# CONNECTOR.net
KiCad netlist of a schematic drawn in Altium Designer
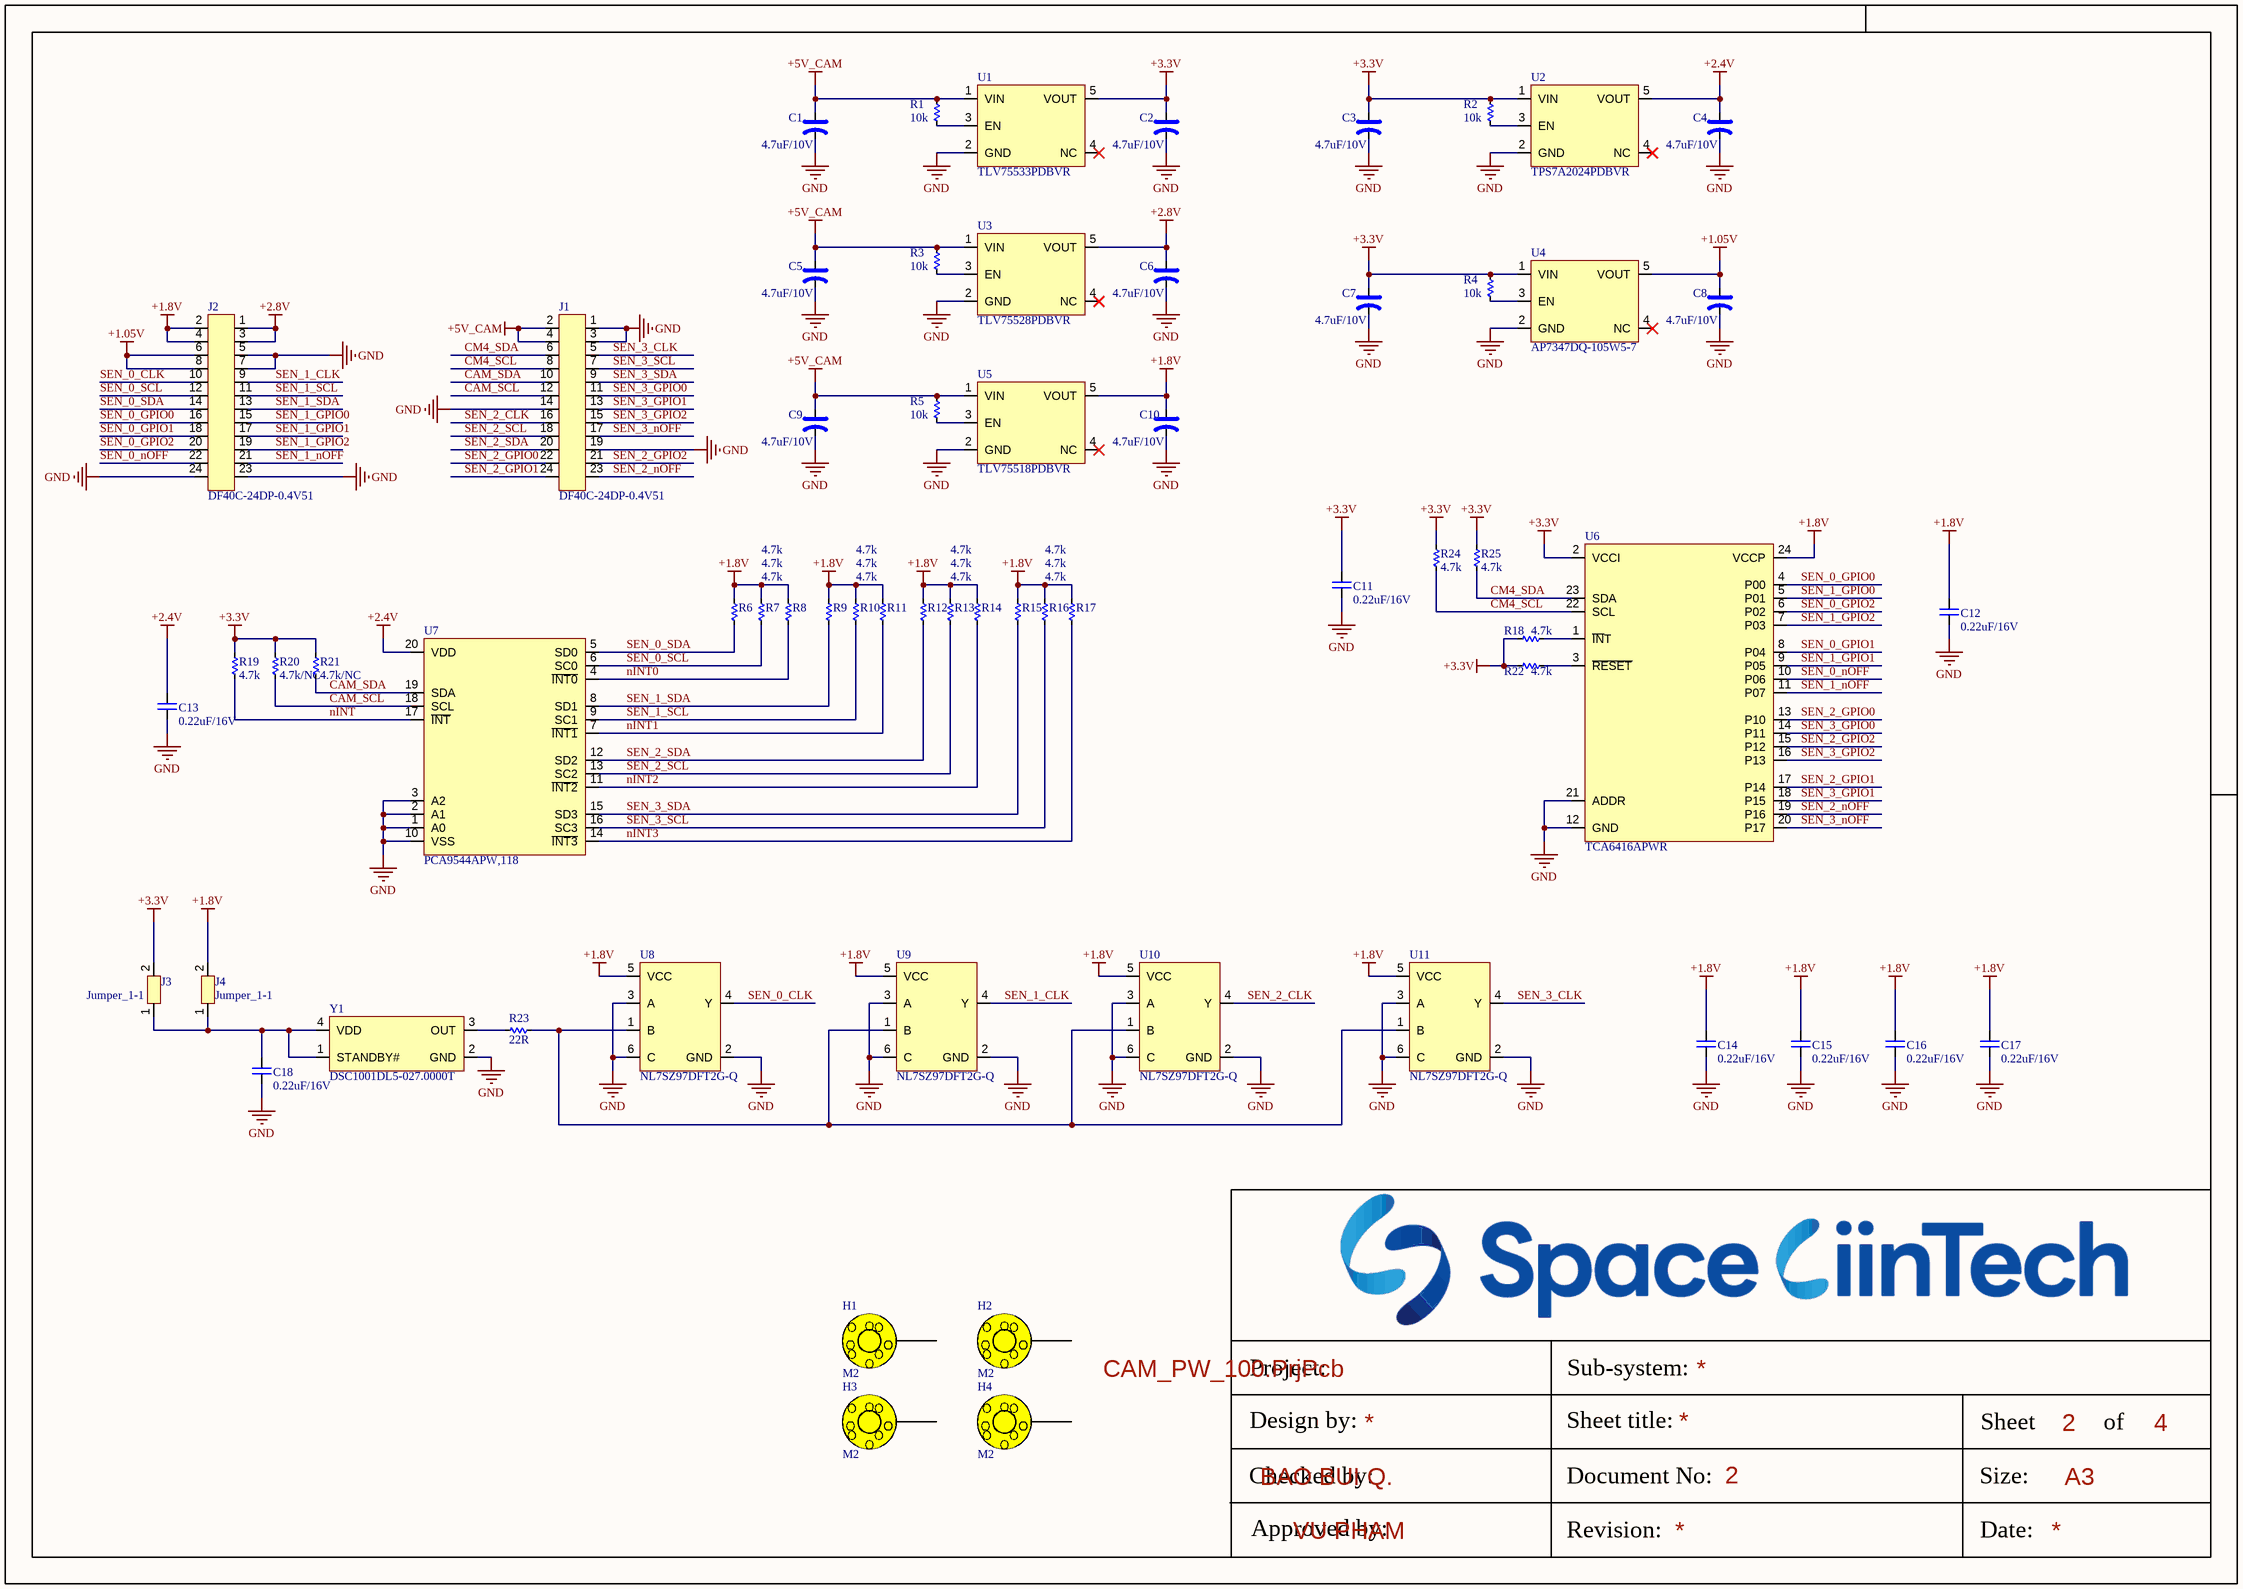
[diagram p0: CONNECTOR.SchDoc]

(export (version "E")
  (design (tool "Eeschema 10.0.6"))
  (components
    (comp (ref "C1")
      (value "4.7uF/10V")
      (footprint "CAP_MP_1608X90")
      (description "CAP_Polarization")
      (fields (field (name "PUBLISHER") "Altium Limited"))
      (libsource (lib "LABLIB") (part "CAP_TH"))
    )
    (comp (ref "C2")
      (value "4.7uF/10V")
      (footprint "CAP_MP_1608X90")
      (description "CAP_Polarization")
      (fields (field (name "PUBLISHER") "Altium Limited"))
      (libsource (lib "LABLIB") (part "CAP_TH"))
    )
    (comp (ref "C3")
      (value "4.7uF/10V")
      (footprint "CAP_MP_1608X90")
      (description "CAP_Polarization")
      (fields (field (name "PUBLISHER") "Altium Limited"))
      (libsource (lib "LABLIB") (part "CAP_TH"))
    )
    (comp (ref "C4")
      (value "4.7uF/10V")
      (footprint "CAP_MP_1608X90")
      (description "CAP_Polarization")
      (fields (field (name "PUBLISHER") "Altium Limited"))
      (libsource (lib "LABLIB") (part "CAP_TH"))
    )
    (comp (ref "C5")
      (value "4.7uF/10V")
      (footprint "CAP_MP_1608X90")
      (description "CAP_Polarization")
      (fields (field (name "PUBLISHER") "Altium Limited"))
      (libsource (lib "LABLIB") (part "CAP_TH"))
    )
    (comp (ref "C6")
      (value "4.7uF/10V")
      (footprint "CAP_MP_1608X90")
      (description "CAP_Polarization")
      (fields (field (name "PUBLISHER") "Altium Limited"))
      (libsource (lib "LABLIB") (part "CAP_TH"))
    )
    (comp (ref "C7")
      (value "4.7uF/10V")
      (footprint "CAP_MP_1608X90")
      (description "CAP_Polarization")
      (fields (field (name "PUBLISHER") "Altium Limited"))
      (libsource (lib "LABLIB") (part "CAP_TH"))
    )
    (comp (ref "C8")
      (value "4.7uF/10V")
      (footprint "CAP_MP_1608X90")
      (description "CAP_Polarization")
      (fields (field (name "PUBLISHER") "Altium Limited"))
      (libsource (lib "LABLIB") (part "CAP_TH"))
    )
    (comp (ref "C9")
      (value "4.7uF/10V")
      (footprint "CAP_MP_1608X90")
      (description "CAP_Polarization")
      (fields (field (name "PUBLISHER") "Altium Limited"))
      (libsource (lib "LABLIB") (part "CAP_TH"))
    )
    (comp (ref "C10")
      (value "4.7uF/10V")
      (footprint "CAP_MP_1608X90")
      (description "CAP_Polarization")
      (fields (field (name "PUBLISHER") "Altium Limited"))
      (libsource (lib "LABLIB") (part "CAP_TH"))
    )
    (comp (ref "C11")
      (value "0.22uF/16V")
      (footprint "CAP_C_1005X60")
      (description "CAP_Chip")
      (libsource (lib "LABLIB") (part "CAP_SMD"))
    )
    (comp (ref "C12")
      (value "0.22uF/16V")
      (footprint "CAP_C_1005X60")
      (description "CAP_Chip")
      (libsource (lib "LABLIB") (part "CAP_SMD"))
    )
    (comp (ref "C13")
      (value "0.22uF/16V")
      (footprint "CAP_C_1005X60")
      (description "CAP_Chip")
      (libsource (lib "LABLIB") (part "CAP_SMD"))
    )
    (comp (ref "C14")
      (value "0.22uF/16V")
      (footprint "CAP_C_1005X60")
      (description "CAP_Chip")
      (libsource (lib "LABLIB") (part "CAP_SMD"))
    )
    (comp (ref "C15")
      (value "0.22uF/16V")
      (footprint "CAP_C_1005X60")
      (description "CAP_Chip")
      (libsource (lib "LABLIB") (part "CAP_SMD"))
    )
    (comp (ref "C16")
      (value "0.22uF/16V")
      (footprint "CAP_C_1005X60")
      (description "CAP_Chip")
      (libsource (lib "LABLIB") (part "CAP_SMD"))
    )
    (comp (ref "C17")
      (value "0.22uF/16V")
      (footprint "CAP_C_1005X60")
      (description "CAP_Chip")
      (libsource (lib "LABLIB") (part "CAP_SMD"))
    )
    (comp (ref "C18")
      (value "0.22uF/16V")
      (footprint "CAP_C_1005X60")
      (description "CAP_Chip")
      (libsource (lib "LABLIB") (part "CAP_SMD"))
    )
    (comp (ref "H1") (value "M2") (footprint "HEX-2.2mm") (libsource (lib "hex_M3") (part "HEX-M3")))
    (comp (ref "H2") (value "M2") (footprint "HEX-2.2mm") (libsource (lib "hex_M3") (part "HEX-M3")))
    (comp (ref "H3") (value "M2") (footprint "HEX-2.2mm") (libsource (lib "hex_M3") (part "HEX-M3")))
    (comp (ref "H4") (value "M2") (footprint "HEX-2.2mm") (libsource (lib "hex_M3") (part "HEX-M3")))
    (comp (ref "J1")
      (value "DF40C-24DP-0.4V51")
      (footprint "CONN24_6p32X1p85_hdr_HIR")
      (description "No Description Available")
      (libsource (lib "CAMERA_SchLib") (part "DF40C-24DP-0.4V51"))
    )
    (comp (ref "J2")
      (value "DF40C-24DP-0.4V51")
      (footprint "CONN24_6p32X1p85_hdr_HIR")
      (description "No Description Available")
      (libsource (lib "CAMERA_SchLib") (part "DF40C-24DP-0.4V51"))
    )
    (comp (ref "J3")
      (value "Jumper_1-1")
      (footprint "Jumper_1-1")
      (libsource (lib "CAMERA_SchLib") (part "Jumper_1_1"))
    )
    (comp (ref "J4")
      (value "Jumper_1-1")
      (footprint "Jumper_1-1")
      (libsource (lib "CAMERA_SchLib") (part "Jumper_1_1"))
    )
    (comp (ref "R1")
      (value "10k")
      (footprint "RES_C_1005X40")
      (description "RES-Chip")
      (fields
        (field (name "MANUFACTURER") "Generic Components")
        (field (name "PUBLISHER") "Altium Hobart Technology Centre")
      )
      (libsource (lib "LABLIB") (part "RES-SMD"))
    )
    (comp (ref "R2")
      (value "10k")
      (footprint "RES_C_1005X40")
      (description "RES-Chip")
      (fields
        (field (name "MANUFACTURER") "Generic Components")
        (field (name "PUBLISHER") "Altium Hobart Technology Centre")
      )
      (libsource (lib "LABLIB") (part "RES-SMD"))
    )
    (comp (ref "R3")
      (value "10k")
      (footprint "RES_C_1005X40")
      (description "RES-Chip")
      (fields
        (field (name "MANUFACTURER") "Generic Components")
        (field (name "PUBLISHER") "Altium Hobart Technology Centre")
      )
      (libsource (lib "LABLIB") (part "RES-SMD"))
    )
    (comp (ref "R4")
      (value "10k")
      (footprint "RES_C_1005X40")
      (description "RES-Chip")
      (fields
        (field (name "MANUFACTURER") "Generic Components")
        (field (name "PUBLISHER") "Altium Hobart Technology Centre")
      )
      (libsource (lib "LABLIB") (part "RES-SMD"))
    )
    (comp (ref "R5")
      (value "10k")
      (footprint "RES_C_1005X40")
      (description "RES-Chip")
      (fields
        (field (name "MANUFACTURER") "Generic Components")
        (field (name "PUBLISHER") "Altium Hobart Technology Centre")
      )
      (libsource (lib "LABLIB") (part "RES-SMD"))
    )
    (comp (ref "R6")
      (value "4.7k")
      (footprint "RES_C_1005X40")
      (description "RES-Chip")
      (fields
        (field (name "MANUFACTURER") "Generic Components")
        (field (name "PUBLISHER") "Altium Hobart Technology Centre")
      )
      (libsource (lib "LABLIB") (part "RES-SMD"))
    )
    (comp (ref "R7")
      (value "4.7k")
      (footprint "RES_C_1005X40")
      (description "RES-Chip")
      (fields
        (field (name "MANUFACTURER") "Generic Components")
        (field (name "PUBLISHER") "Altium Hobart Technology Centre")
      )
      (libsource (lib "LABLIB") (part "RES-SMD"))
    )
    (comp (ref "R8")
      (value "4.7k")
      (footprint "RES_C_1005X40")
      (description "RES-Chip")
      (fields
        (field (name "MANUFACTURER") "Generic Components")
        (field (name "PUBLISHER") "Altium Hobart Technology Centre")
      )
      (libsource (lib "LABLIB") (part "RES-SMD"))
    )
    (comp (ref "R9")
      (value "4.7k")
      (footprint "RES_C_1005X40")
      (description "RES-Chip")
      (fields
        (field (name "MANUFACTURER") "Generic Components")
        (field (name "PUBLISHER") "Altium Hobart Technology Centre")
      )
      (libsource (lib "LABLIB") (part "RES-SMD"))
    )
    (comp (ref "R10")
      (value "4.7k")
      (footprint "RES_C_1005X40")
      (description "RES-Chip")
      (fields
        (field (name "MANUFACTURER") "Generic Components")
        (field (name "PUBLISHER") "Altium Hobart Technology Centre")
      )
      (libsource (lib "LABLIB") (part "RES-SMD"))
    )
    (comp (ref "R11")
      (value "4.7k")
      (footprint "RES_C_1005X40")
      (description "RES-Chip")
      (fields
        (field (name "MANUFACTURER") "Generic Components")
        (field (name "PUBLISHER") "Altium Hobart Technology Centre")
      )
      (libsource (lib "LABLIB") (part "RES-SMD"))
    )
    (comp (ref "R12")
      (value "4.7k")
      (footprint "RES_C_1005X40")
      (description "RES-Chip")
      (fields
        (field (name "MANUFACTURER") "Generic Components")
        (field (name "PUBLISHER") "Altium Hobart Technology Centre")
      )
      (libsource (lib "LABLIB") (part "RES-SMD"))
    )
    (comp (ref "R13")
      (value "4.7k")
      (footprint "RES_C_1005X40")
      (description "RES-Chip")
      (fields
        (field (name "MANUFACTURER") "Generic Components")
        (field (name "PUBLISHER") "Altium Hobart Technology Centre")
      )
      (libsource (lib "LABLIB") (part "RES-SMD"))
    )
    (comp (ref "R14")
      (value "4.7k")
      (footprint "RES_C_1005X40")
      (description "RES-Chip")
      (fields
        (field (name "MANUFACTURER") "Generic Components")
        (field (name "PUBLISHER") "Altium Hobart Technology Centre")
      )
      (libsource (lib "LABLIB") (part "RES-SMD"))
    )
    (comp (ref "R15")
      (value "4.7k")
      (footprint "RES_C_1005X40")
      (description "RES-Chip")
      (fields
        (field (name "MANUFACTURER") "Generic Components")
        (field (name "PUBLISHER") "Altium Hobart Technology Centre")
      )
      (libsource (lib "LABLIB") (part "RES-SMD"))
    )
    (comp (ref "R16")
      (value "4.7k")
      (footprint "RES_C_1005X40")
      (description "RES-Chip")
      (fields
        (field (name "MANUFACTURER") "Generic Components")
        (field (name "PUBLISHER") "Altium Hobart Technology Centre")
      )
      (libsource (lib "LABLIB") (part "RES-SMD"))
    )
    (comp (ref "R17")
      (value "4.7k")
      (footprint "RES_C_1005X40")
      (description "RES-Chip")
      (fields
        (field (name "MANUFACTURER") "Generic Components")
        (field (name "PUBLISHER") "Altium Hobart Technology Centre")
      )
      (libsource (lib "LABLIB") (part "RES-SMD"))
    )
    (comp (ref "R18")
      (value "4.7k")
      (footprint "RES_C_1005X40")
      (description "RES-Chip")
      (fields
        (field (name "MANUFACTURER") "Generic Components")
        (field (name "PUBLISHER") "Altium Hobart Technology Centre")
      )
      (libsource (lib "LABLIB") (part "RES-SMD"))
    )
    (comp (ref "R19")
      (value "4.7k")
      (footprint "RES_C_1005X40")
      (description "RES-Chip")
      (fields
        (field (name "MANUFACTURER") "Generic Components")
        (field (name "PUBLISHER") "Altium Hobart Technology Centre")
      )
      (libsource (lib "LABLIB") (part "RES-SMD"))
    )
    (comp (ref "R20")
      (value "4.7k/NC")
      (footprint "RES_C_1005X40")
      (description "RES-Chip")
      (fields
        (field (name "MANUFACTURER") "Generic Components")
        (field (name "PUBLISHER") "Altium Hobart Technology Centre")
      )
      (libsource (lib "LABLIB") (part "RES-SMD"))
    )
    (comp (ref "R21")
      (value "4.7k/NC")
      (footprint "RES_C_1005X40")
      (description "RES-Chip")
      (fields
        (field (name "MANUFACTURER") "Generic Components")
        (field (name "PUBLISHER") "Altium Hobart Technology Centre")
      )
      (libsource (lib "LABLIB") (part "RES-SMD"))
    )
    (comp (ref "R22")
      (value "4.7k")
      (footprint "RES_C_1005X40")
      (description "RES-Chip")
      (fields
        (field (name "MANUFACTURER") "Generic Components")
        (field (name "PUBLISHER") "Altium Hobart Technology Centre")
      )
      (libsource (lib "LABLIB") (part "RES-SMD"))
    )
    (comp (ref "R23")
      (value "22R")
      (footprint "RES_C_1005X40")
      (description "RES-Chip")
      (fields
        (field (name "MANUFACTURER") "Generic Components")
        (field (name "PUBLISHER") "Altium Hobart Technology Centre")
      )
      (libsource (lib "LABLIB") (part "RES-SMD"))
    )
    (comp (ref "R24")
      (value "4.7k")
      (footprint "RES_C_1005X40")
      (description "RES-Chip")
      (fields
        (field (name "MANUFACTURER") "Generic Components")
        (field (name "PUBLISHER") "Altium Hobart Technology Centre")
      )
      (libsource (lib "LABLIB") (part "RES-SMD"))
    )
    (comp (ref "R25")
      (value "4.7k")
      (footprint "RES_C_1005X40")
      (description "RES-Chip")
      (fields
        (field (name "MANUFACTURER") "Generic Components")
        (field (name "PUBLISHER") "Altium Hobart Technology Centre")
      )
      (libsource (lib "LABLIB") (part "RES-SMD"))
    )
    (comp (ref "U1")
      (value "TLV75533PDBVR")
      (footprint "SOT25")
      (libsource (lib "CAMERA_SchLib") (part "IC_POWER_AP7347DQ"))
    )
    (comp (ref "U2")
      (value "TPS7A2024PDBVR")
      (footprint "SOT25")
      (libsource (lib "CAMERA_SchLib") (part "IC_POWER_AP7347DQ"))
    )
    (comp (ref "U3")
      (value "TLV75528PDBVR")
      (footprint "SOT25")
      (libsource (lib "CAMERA_SchLib") (part "IC_POWER_AP7347DQ"))
    )
    (comp (ref "U4")
      (value "AP7347DQ-105W5-7")
      (footprint "SOT25")
      (libsource (lib "CAMERA_SchLib") (part "IC_POWER_AP7347DQ"))
    )
    (comp (ref "U5")
      (value "TLV75518PDBVR")
      (footprint "SOT25")
      (libsource (lib "CAMERA_SchLib") (part "IC_POWER_AP7347DQ"))
    )
    (comp (ref "U6")
      (value "TCA6416APWR")
      (footprint "SOP65P440W-24N")
      (libsource (lib "CAMERA_SchLib") (part "IC_I2Cto16IO_TCA6416APWR"))
    )
    (comp (ref "U7")
      (value "PCA9544APW,118")
      (footprint "SOP65P440W_20")
      (libsource (lib "CAMERA_SchLib") (part "IC_I2CSW1to4_PCA9544APW,118"))
    )
    (comp (ref "U8")
      (value "NL7SZ97DFT2G-Q")
      (footprint "SC-88")
      (libsource (lib "CAMERA_SchLib") (part "IC_FLEXLOGIC_NL7SZ97DFT2G-Q"))
    )
    (comp (ref "U9")
      (value "NL7SZ97DFT2G-Q")
      (footprint "SC-88")
      (libsource (lib "CAMERA_SchLib") (part "IC_FLEXLOGIC_NL7SZ97DFT2G-Q"))
    )
    (comp (ref "U10")
      (value "NL7SZ97DFT2G-Q")
      (footprint "SC-88")
      (libsource (lib "CAMERA_SchLib") (part "IC_FLEXLOGIC_NL7SZ97DFT2G-Q"))
    )
    (comp (ref "U11")
      (value "NL7SZ97DFT2G-Q")
      (footprint "SC-88")
      (libsource (lib "CAMERA_SchLib") (part "IC_FLEXLOGIC_NL7SZ97DFT2G-Q"))
    )
    (comp (ref "Y1")
      (value "DSC1001DL5-027.0000T")
      (footprint "OSCDFN250X200X89-4N")
      (libsource (lib "CAMERA_SchLib") (part "Y_OSC27MHz_DSC1001DL5-027.0000T"))
    )
  )
  (nets
    (net (code "1") (name "+1.05V") (class "Default")
      (node (ref "C8") (pin "1") (pinfunction "1_1") (pintype "passive"))
      (node (ref "J2") (pin "6") (pintype "passive"))
      (node (ref "J2") (pin "8") (pintype "passive"))
      (node (ref "U4") (pin "5") (pinfunction "VOUT_5") (pintype "passive"))
    )
    (net (code "2") (name "+1.8V") (class "Default")
      (node (ref "C10") (pin "1") (pinfunction "1_1") (pintype "passive"))
      (node (ref "C12") (pin "2") (pinfunction "2_2") (pintype "passive"))
      (node (ref "C14") (pin "2") (pinfunction "2_2") (pintype "passive"))
      (node (ref "C15") (pin "2") (pinfunction "2_2") (pintype "passive"))
      (node (ref "C16") (pin "2") (pinfunction "2_2") (pintype "passive"))
      (node (ref "C17") (pin "2") (pinfunction "2_2") (pintype "passive"))
      (node (ref "J2") (pin "2") (pintype "passive"))
      (node (ref "J2") (pin "4") (pintype "passive"))
      (node (ref "J4") (pin "2") (pintype "passive"))
      (node (ref "R10") (pin "1") (pinfunction "1_1") (pintype "passive"))
      (node (ref "R11") (pin "1") (pinfunction "1_1") (pintype "passive"))
      (node (ref "R12") (pin "1") (pinfunction "1_1") (pintype "passive"))
      (node (ref "R13") (pin "1") (pinfunction "1_1") (pintype "passive"))
      (node (ref "R14") (pin "1") (pinfunction "1_1") (pintype "passive"))
      (node (ref "R15") (pin "1") (pinfunction "1_1") (pintype "passive"))
      (node (ref "R16") (pin "1") (pinfunction "1_1") (pintype "passive"))
      (node (ref "R17") (pin "1") (pinfunction "1_1") (pintype "passive"))
      (node (ref "R6") (pin "1") (pinfunction "1_1") (pintype "passive"))
      (node (ref "R7") (pin "1") (pinfunction "1_1") (pintype "passive"))
      (node (ref "R8") (pin "1") (pinfunction "1_1") (pintype "passive"))
      (node (ref "R9") (pin "1") (pinfunction "1_1") (pintype "passive"))
      (node (ref "U10") (pin "5") (pinfunction "VCC_5") (pintype "passive"))
      (node (ref "U11") (pin "5") (pinfunction "VCC_5") (pintype "passive"))
      (node (ref "U5") (pin "5") (pinfunction "VOUT_5") (pintype "passive"))
      (node (ref "U6") (pin "24") (pinfunction "VCCP_24") (pintype "passive"))
      (node (ref "U8") (pin "5") (pinfunction "VCC_5") (pintype "passive"))
      (node (ref "U9") (pin "5") (pinfunction "VCC_5") (pintype "passive"))
    )
    (net (code "3") (name "+2.4V") (class "Default")
      (node (ref "C13") (pin "2") (pinfunction "2_2") (pintype "passive"))
      (node (ref "C4") (pin "1") (pinfunction "1_1") (pintype "passive"))
      (node (ref "U2") (pin "5") (pinfunction "VOUT_5") (pintype "passive"))
      (node (ref "U7") (pin "20") (pinfunction "VDD_20") (pintype "passive"))
    )
    (net (code "4") (name "+2.8V") (class "Default")
      (node (ref "C6") (pin "1") (pinfunction "1_1") (pintype "passive"))
      (node (ref "J2") (pin "1") (pintype "passive"))
      (node (ref "J2") (pin "3") (pintype "passive"))
      (node (ref "U3") (pin "5") (pinfunction "VOUT_5") (pintype "passive"))
    )
    (net (code "5") (name "+3.3V") (class "Default")
      (node (ref "C11") (pin "2") (pinfunction "2_2") (pintype "passive"))
      (node (ref "C2") (pin "1") (pinfunction "1_1") (pintype "passive"))
      (node (ref "C3") (pin "1") (pinfunction "1_1") (pintype "passive"))
      (node (ref "C7") (pin "1") (pinfunction "1_1") (pintype "passive"))
      (node (ref "J3") (pin "2") (pintype "passive"))
      (node (ref "R18") (pin "1") (pinfunction "1_1") (pintype "passive"))
      (node (ref "R19") (pin "1") (pinfunction "1_1") (pintype "passive"))
      (node (ref "R2") (pin "2") (pinfunction "2_2") (pintype "passive"))
      (node (ref "R20") (pin "1") (pinfunction "1_1") (pintype "passive"))
      (node (ref "R21") (pin "1") (pinfunction "1_1") (pintype "passive"))
      (node (ref "R22") (pin "1") (pinfunction "1_1") (pintype "passive"))
      (node (ref "R24") (pin "1") (pinfunction "1_1") (pintype "passive"))
      (node (ref "R25") (pin "1") (pinfunction "1_1") (pintype "passive"))
      (node (ref "R4") (pin "2") (pinfunction "2_2") (pintype "passive"))
      (node (ref "U1") (pin "5") (pinfunction "VOUT_5") (pintype "passive"))
      (node (ref "U2") (pin "1") (pinfunction "VIN_1") (pintype "passive"))
      (node (ref "U4") (pin "1") (pinfunction "VIN_1") (pintype "passive"))
      (node (ref "U6") (pin "2") (pinfunction "VCCI_2") (pintype "passive"))
    )
    (net (code "6") (name "+5V_CAM") (class "Default")
      (node (ref "C1") (pin "1") (pinfunction "1_1") (pintype "passive"))
      (node (ref "C5") (pin "1") (pinfunction "1_1") (pintype "passive"))
      (node (ref "C9") (pin "1") (pinfunction "1_1") (pintype "passive"))
      (node (ref "J1") (pin "2") (pintype "passive"))
      (node (ref "J1") (pin "4") (pintype "passive"))
      (node (ref "R1") (pin "2") (pinfunction "2_2") (pintype "passive"))
      (node (ref "R3") (pin "2") (pinfunction "2_2") (pintype "passive"))
      (node (ref "R5") (pin "2") (pinfunction "2_2") (pintype "passive"))
      (node (ref "U1") (pin "1") (pinfunction "VIN_1") (pintype "passive"))
      (node (ref "U3") (pin "1") (pinfunction "VIN_1") (pintype "passive"))
      (node (ref "U5") (pin "1") (pinfunction "VIN_1") (pintype "passive"))
    )
    (net (code "7") (name "/CAM_SCL") (class "Default")
      (node (ref "J1") (pin "12") (pintype "passive"))
      (node (ref "R20") (pin "2") (pinfunction "2_2") (pintype "passive"))
      (node (ref "U7") (pin "18") (pinfunction "SCL_18") (pintype "passive"))
    )
    (net (code "8") (name "/CAM_SDA") (class "Default")
      (node (ref "J1") (pin "10") (pintype "passive"))
      (node (ref "R21") (pin "2") (pinfunction "2_2") (pintype "passive"))
      (node (ref "U7") (pin "19") (pinfunction "SDA_19") (pintype "passive"))
    )
    (net (code "9") (name "/CM4_SCL") (class "Default")
      (node (ref "J1") (pin "8") (pintype "passive"))
      (node (ref "R24") (pin "2") (pinfunction "2_2") (pintype "passive"))
      (node (ref "U6") (pin "22") (pinfunction "SCL_22") (pintype "passive"))
    )
    (net (code "10") (name "/CM4_SDA") (class "Default")
      (node (ref "J1") (pin "6") (pintype "passive"))
      (node (ref "R25") (pin "2") (pinfunction "2_2") (pintype "passive"))
      (node (ref "U6") (pin "23") (pinfunction "SDA_23") (pintype "passive"))
    )
    (net (code "11") (name "/SEN_0_CLK") (class "Default")
      (node (ref "J2") (pin "10") (pintype "passive"))
      (node (ref "U8") (pin "4") (pinfunction "Y_4") (pintype "passive"))
    )
    (net (code "12") (name "/SEN_0_GPIO0") (class "Default")
      (node (ref "J2") (pin "16") (pintype "passive"))
      (node (ref "U6") (pin "4") (pinfunction "P00_4") (pintype "passive"))
    )
    (net (code "13") (name "/SEN_0_GPIO1") (class "Default")
      (node (ref "J2") (pin "18") (pintype "passive"))
      (node (ref "U6") (pin "8") (pinfunction "P04_8") (pintype "passive"))
    )
    (net (code "14") (name "/SEN_0_GPIO2") (class "Default")
      (node (ref "J2") (pin "20") (pintype "passive"))
      (node (ref "U6") (pin "6") (pinfunction "P02_6") (pintype "passive"))
    )
    (net (code "15") (name "/SEN_0_SCL") (class "Default")
      (node (ref "J2") (pin "12") (pintype "passive"))
      (node (ref "R7") (pin "2") (pinfunction "2_2") (pintype "passive"))
      (node (ref "U7") (pin "6") (pinfunction "SC0_6") (pintype "passive"))
    )
    (net (code "16") (name "/SEN_0_SDA") (class "Default")
      (node (ref "J2") (pin "14") (pintype "passive"))
      (node (ref "R6") (pin "2") (pinfunction "2_2") (pintype "passive"))
      (node (ref "U7") (pin "5") (pinfunction "SD0_5") (pintype "passive"))
    )
    (net (code "17") (name "/SEN_0_nOFF") (class "Default")
      (node (ref "J2") (pin "22") (pintype "passive"))
      (node (ref "U6") (pin "10") (pinfunction "P06_10") (pintype "passive"))
    )
    (net (code "18") (name "/SEN_1_CLK") (class "Default")
      (node (ref "J2") (pin "9") (pintype "passive"))
      (node (ref "U9") (pin "4") (pinfunction "Y_4") (pintype "passive"))
    )
    (net (code "19") (name "/SEN_1_GPIO0") (class "Default")
      (node (ref "J2") (pin "15") (pintype "passive"))
      (node (ref "U6") (pin "5") (pinfunction "P01_5") (pintype "passive"))
    )
    (net (code "20") (name "/SEN_1_GPIO1") (class "Default")
      (node (ref "J2") (pin "17") (pintype "passive"))
      (node (ref "U6") (pin "9") (pinfunction "P05_9") (pintype "passive"))
    )
    (net (code "21") (name "/SEN_1_GPIO2") (class "Default")
      (node (ref "J2") (pin "19") (pintype "passive"))
      (node (ref "U6") (pin "7") (pinfunction "P03_7") (pintype "passive"))
    )
    (net (code "22") (name "/SEN_1_SCL") (class "Default")
      (node (ref "J2") (pin "11") (pintype "passive"))
      (node (ref "R10") (pin "2") (pinfunction "2_2") (pintype "passive"))
      (node (ref "U7") (pin "9") (pinfunction "SC1_9") (pintype "passive"))
    )
    (net (code "23") (name "/SEN_1_SDA") (class "Default")
      (node (ref "J2") (pin "13") (pintype "passive"))
      (node (ref "R9") (pin "2") (pinfunction "2_2") (pintype "passive"))
      (node (ref "U7") (pin "8") (pinfunction "SD1_8") (pintype "passive"))
    )
    (net (code "24") (name "/SEN_1_nOFF") (class "Default")
      (node (ref "J2") (pin "21") (pintype "passive"))
      (node (ref "U6") (pin "11") (pinfunction "P07_11") (pintype "passive"))
    )
    (net (code "25") (name "/SEN_2_CLK") (class "Default")
      (node (ref "J1") (pin "16") (pintype "passive"))
      (node (ref "U10") (pin "4") (pinfunction "Y_4") (pintype "passive"))
    )
    (net (code "26") (name "/SEN_2_GPIO0") (class "Default")
      (node (ref "J1") (pin "22") (pintype "passive"))
      (node (ref "U6") (pin "13") (pinfunction "P10_13") (pintype "passive"))
    )
    (net (code "27") (name "/SEN_2_GPIO1") (class "Default")
      (node (ref "J1") (pin "24") (pintype "passive"))
      (node (ref "U6") (pin "17") (pinfunction "P14_17") (pintype "passive"))
    )
    (net (code "28") (name "/SEN_2_GPIO2") (class "Default")
      (node (ref "J1") (pin "21") (pintype "passive"))
      (node (ref "U6") (pin "15") (pinfunction "P12_15") (pintype "passive"))
    )
    (net (code "29") (name "/SEN_2_SCL") (class "Default")
      (node (ref "J1") (pin "18") (pintype "passive"))
      (node (ref "R13") (pin "2") (pinfunction "2_2") (pintype "passive"))
      (node (ref "U7") (pin "13") (pinfunction "SC2_13") (pintype "passive"))
    )
    (net (code "30") (name "/SEN_2_SDA") (class "Default")
      (node (ref "J1") (pin "20") (pintype "passive"))
      (node (ref "R12") (pin "2") (pinfunction "2_2") (pintype "passive"))
      (node (ref "U7") (pin "12") (pinfunction "SD2_12") (pintype "passive"))
    )
    (net (code "31") (name "/SEN_2_nOFF") (class "Default")
      (node (ref "J1") (pin "23") (pintype "passive"))
      (node (ref "U6") (pin "19") (pinfunction "P16_19") (pintype "passive"))
    )
    (net (code "32") (name "/SEN_3_CLK") (class "Default")
      (node (ref "J1") (pin "5") (pintype "passive"))
      (node (ref "U11") (pin "4") (pinfunction "Y_4") (pintype "passive"))
    )
    (net (code "33") (name "/SEN_3_GPIO0") (class "Default")
      (node (ref "J1") (pin "11") (pintype "passive"))
      (node (ref "U6") (pin "14") (pinfunction "P11_14") (pintype "passive"))
    )
    (net (code "34") (name "/SEN_3_GPIO1") (class "Default")
      (node (ref "J1") (pin "13") (pintype "passive"))
      (node (ref "U6") (pin "18") (pinfunction "P15_18") (pintype "passive"))
    )
    (net (code "35") (name "/SEN_3_GPIO2") (class "Default")
      (node (ref "J1") (pin "15") (pintype "passive"))
      (node (ref "U6") (pin "16") (pinfunction "P13_16") (pintype "passive"))
    )
    (net (code "36") (name "/SEN_3_SCL") (class "Default")
      (node (ref "J1") (pin "7") (pintype "passive"))
      (node (ref "R16") (pin "2") (pinfunction "2_2") (pintype "passive"))
      (node (ref "U7") (pin "16") (pinfunction "SC3_16") (pintype "passive"))
    )
    (net (code "37") (name "/SEN_3_SDA") (class "Default")
      (node (ref "J1") (pin "9") (pintype "passive"))
      (node (ref "R15") (pin "2") (pinfunction "2_2") (pintype "passive"))
      (node (ref "U7") (pin "15") (pinfunction "SD3_15") (pintype "passive"))
    )
    (net (code "38") (name "/SEN_3_nOFF") (class "Default")
      (node (ref "J1") (pin "17") (pintype "passive"))
      (node (ref "U6") (pin "20") (pinfunction "P17_20") (pintype "passive"))
    )
    (net (code "39") (name "/nINT") (class "Default")
      (node (ref "R19") (pin "2") (pinfunction "2_2") (pintype "passive"))
      (node (ref "U7") (pin "17") (pinfunction "~{INT}_17") (pintype "passive"))
    )
    (net (code "40") (name "/nINT0") (class "Default")
      (node (ref "R8") (pin "2") (pinfunction "2_2") (pintype "passive"))
      (node (ref "U7") (pin "4") (pinfunction "~{INT0}_4") (pintype "passive"))
    )
    (net (code "41") (name "/nINT1") (class "Default")
      (node (ref "R11") (pin "2") (pinfunction "2_2") (pintype "passive"))
      (node (ref "U7") (pin "7") (pinfunction "~{INT1}_7") (pintype "passive"))
    )
    (net (code "42") (name "/nINT2") (class "Default")
      (node (ref "R14") (pin "2") (pinfunction "2_2") (pintype "passive"))
      (node (ref "U7") (pin "11") (pinfunction "~{INT2}_11") (pintype "passive"))
    )
    (net (code "43") (name "/nINT3") (class "Default")
      (node (ref "R17") (pin "2") (pinfunction "2_2") (pintype "passive"))
      (node (ref "U7") (pin "14") (pinfunction "~{INT3}_14") (pintype "passive"))
    )
    (net (code "44") (name "GND") (class "Default")
      (node (ref "C1") (pin "2") (pinfunction "2_2") (pintype "passive"))
      (node (ref "C10") (pin "2") (pinfunction "2_2") (pintype "passive"))
      (node (ref "C11") (pin "1") (pinfunction "1_1") (pintype "passive"))
      (node (ref "C12") (pin "1") (pinfunction "1_1") (pintype "passive"))
      (node (ref "C13") (pin "1") (pinfunction "1_1") (pintype "passive"))
      (node (ref "C14") (pin "1") (pinfunction "1_1") (pintype "passive"))
      (node (ref "C15") (pin "1") (pinfunction "1_1") (pintype "passive"))
      (node (ref "C16") (pin "1") (pinfunction "1_1") (pintype "passive"))
      (node (ref "C17") (pin "1") (pinfunction "1_1") (pintype "passive"))
      (node (ref "C18") (pin "1") (pinfunction "1_1") (pintype "passive"))
      (node (ref "C2") (pin "2") (pinfunction "2_2") (pintype "passive"))
      (node (ref "C3") (pin "2") (pinfunction "2_2") (pintype "passive"))
      (node (ref "C4") (pin "2") (pinfunction "2_2") (pintype "passive"))
      (node (ref "C5") (pin "2") (pinfunction "2_2") (pintype "passive"))
      (node (ref "C6") (pin "2") (pinfunction "2_2") (pintype "passive"))
      (node (ref "C7") (pin "2") (pinfunction "2_2") (pintype "passive"))
      (node (ref "C8") (pin "2") (pinfunction "2_2") (pintype "passive"))
      (node (ref "C9") (pin "2") (pinfunction "2_2") (pintype "passive"))
      (node (ref "J1") (pin "1") (pintype "passive"))
      (node (ref "J1") (pin "14") (pintype "passive"))
      (node (ref "J1") (pin "19") (pintype "passive"))
      (node (ref "J1") (pin "3") (pintype "passive"))
      (node (ref "J2") (pin "23") (pintype "passive"))
      (node (ref "J2") (pin "24") (pintype "passive"))
      (node (ref "J2") (pin "5") (pintype "passive"))
      (node (ref "J2") (pin "7") (pintype "passive"))
      (node (ref "U1") (pin "2") (pinfunction "GND_2") (pintype "passive"))
      (node (ref "U10") (pin "2") (pinfunction "GND_2") (pintype "passive"))
      (node (ref "U10") (pin "3") (pinfunction "A_3") (pintype "passive"))
      (node (ref "U10") (pin "6") (pinfunction "C_6") (pintype "passive"))
      (node (ref "U11") (pin "2") (pinfunction "GND_2") (pintype "passive"))
      (node (ref "U11") (pin "3") (pinfunction "A_3") (pintype "passive"))
      (node (ref "U11") (pin "6") (pinfunction "C_6") (pintype "passive"))
      (node (ref "U2") (pin "2") (pinfunction "GND_2") (pintype "passive"))
      (node (ref "U3") (pin "2") (pinfunction "GND_2") (pintype "passive"))
      (node (ref "U4") (pin "2") (pinfunction "GND_2") (pintype "passive"))
      (node (ref "U5") (pin "2") (pinfunction "GND_2") (pintype "passive"))
      (node (ref "U6") (pin "12") (pinfunction "GND_12") (pintype "passive"))
      (node (ref "U6") (pin "21") (pinfunction "ADDR_21") (pintype "passive"))
      (node (ref "U7") (pin "1") (pinfunction "A0_1") (pintype "passive"))
      (node (ref "U7") (pin "10") (pinfunction "VSS_10") (pintype "passive"))
      (node (ref "U7") (pin "2") (pinfunction "A1_2") (pintype "passive"))
      (node (ref "U7") (pin "3") (pinfunction "A2_3") (pintype "passive"))
      (node (ref "U8") (pin "2") (pinfunction "GND_2") (pintype "passive"))
      (node (ref "U8") (pin "3") (pinfunction "A_3") (pintype "passive"))
      (node (ref "U8") (pin "6") (pinfunction "C_6") (pintype "passive"))
      (node (ref "U9") (pin "2") (pinfunction "GND_2") (pintype "passive"))
      (node (ref "U9") (pin "3") (pinfunction "A_3") (pintype "passive"))
      (node (ref "U9") (pin "6") (pinfunction "C_6") (pintype "passive"))
      (node (ref "Y1") (pin "2") (pinfunction "GND_2") (pintype "passive"))
    )
    (net (code "45") (name "Net-(U1-EN)") (class "Default")
      (node (ref "R1") (pin "1") (pinfunction "1_1") (pintype "passive"))
      (node (ref "U1") (pin "3") (pinfunction "EN_3") (pintype "passive"))
    )
    (net (code "46") (name "Net-(U2-EN)") (class "Default")
      (node (ref "R2") (pin "1") (pinfunction "1_1") (pintype "passive"))
      (node (ref "U2") (pin "3") (pinfunction "EN_3") (pintype "passive"))
    )
    (net (code "47") (name "Net-(U3-EN)") (class "Default")
      (node (ref "R3") (pin "1") (pinfunction "1_1") (pintype "passive"))
      (node (ref "U3") (pin "3") (pinfunction "EN_3") (pintype "passive"))
    )
    (net (code "48") (name "Net-(U4-EN)") (class "Default")
      (node (ref "R4") (pin "1") (pinfunction "1_1") (pintype "passive"))
      (node (ref "U4") (pin "3") (pinfunction "EN_3") (pintype "passive"))
    )
    (net (code "49") (name "Net-(U5-EN)") (class "Default")
      (node (ref "R5") (pin "1") (pinfunction "1_1") (pintype "passive"))
      (node (ref "U5") (pin "3") (pinfunction "EN_3") (pintype "passive"))
    )
    (net (code "50") (name "Net-(U6-~{IN}T)") (class "Default")
      (node (ref "R18") (pin "2") (pinfunction "2_2") (pintype "passive"))
      (node (ref "U6") (pin "1") (pinfunction "~{IN}T_1") (pintype "passive"))
    )
    (net (code "51") (name "Net-(U6-~{RESET})") (class "Default")
      (node (ref "R22") (pin "2") (pinfunction "2_2") (pintype "passive"))
      (node (ref "U6") (pin "3") (pinfunction "~{RESET}_3") (pintype "passive"))
    )
    (net (code "52") (name "Net-(U10-B)") (class "Default")
      (node (ref "R23") (pin "1") (pinfunction "1_1") (pintype "passive"))
      (node (ref "U10") (pin "1") (pinfunction "B_1") (pintype "passive"))
      (node (ref "U11") (pin "1") (pinfunction "B_1") (pintype "passive"))
      (node (ref "U8") (pin "1") (pinfunction "B_1") (pintype "passive"))
      (node (ref "U9") (pin "1") (pinfunction "B_1") (pintype "passive"))
    )
    (net (code "53") (name "Net-(Y1-OUT)") (class "Default")
      (node (ref "R23") (pin "2") (pinfunction "2_2") (pintype "passive"))
      (node (ref "Y1") (pin "3") (pinfunction "OUT_3") (pintype "passive"))
    )
    (net (code "54") (name "Net-(Y1-STANDBY#)") (class "Default")
      (node (ref "C18") (pin "2") (pinfunction "2_2") (pintype "passive"))
      (node (ref "J3") (pin "1") (pintype "passive"))
      (node (ref "J4") (pin "1") (pintype "passive"))
      (node (ref "Y1") (pin "1") (pinfunction "STANDBY#_1") (pintype "passive"))
      (node (ref "Y1") (pin "4") (pinfunction "VDD_4") (pintype "passive"))
    )
    (net (code "55") (name "unconnected-(H1-Pad1)") (class "Default")
      (node (ref "H1") (pin "1") (pinfunction "1_1") (pintype "power_in"))
    )
    (net (code "56") (name "unconnected-(H2-Pad1)") (class "Default")
      (node (ref "H2") (pin "1") (pinfunction "1_1") (pintype "power_in"))
    )
    (net (code "57") (name "unconnected-(H3-Pad1)") (class "Default")
      (node (ref "H3") (pin "1") (pinfunction "1_1") (pintype "power_in"))
    )
    (net (code "58") (name "unconnected-(H4-Pad1)") (class "Default")
      (node (ref "H4") (pin "1") (pinfunction "1_1") (pintype "power_in"))
    )
    (net (code "59") (name "unconnected-(U1-NC-Pad4)") (class "Default")
      (node (ref "U1") (pin "4") (pinfunction "NC_4") (pintype "passive+no_connect"))
    )
    (net (code "60") (name "unconnected-(U2-NC-Pad4)") (class "Default")
      (node (ref "U2") (pin "4") (pinfunction "NC_4") (pintype "passive+no_connect"))
    )
    (net (code "61") (name "unconnected-(U3-NC-Pad4)") (class "Default")
      (node (ref "U3") (pin "4") (pinfunction "NC_4") (pintype "passive+no_connect"))
    )
    (net (code "62") (name "unconnected-(U4-NC-Pad4)") (class "Default")
      (node (ref "U4") (pin "4") (pinfunction "NC_4") (pintype "passive+no_connect"))
    )
    (net (code "63") (name "unconnected-(U5-NC-Pad4)") (class "Default")
      (node (ref "U5") (pin "4") (pinfunction "NC_4") (pintype "passive+no_connect"))
    )
  )
)
